# atmega_embedded_main.net
KiCad netlist of a schematic drawn in EAGLE
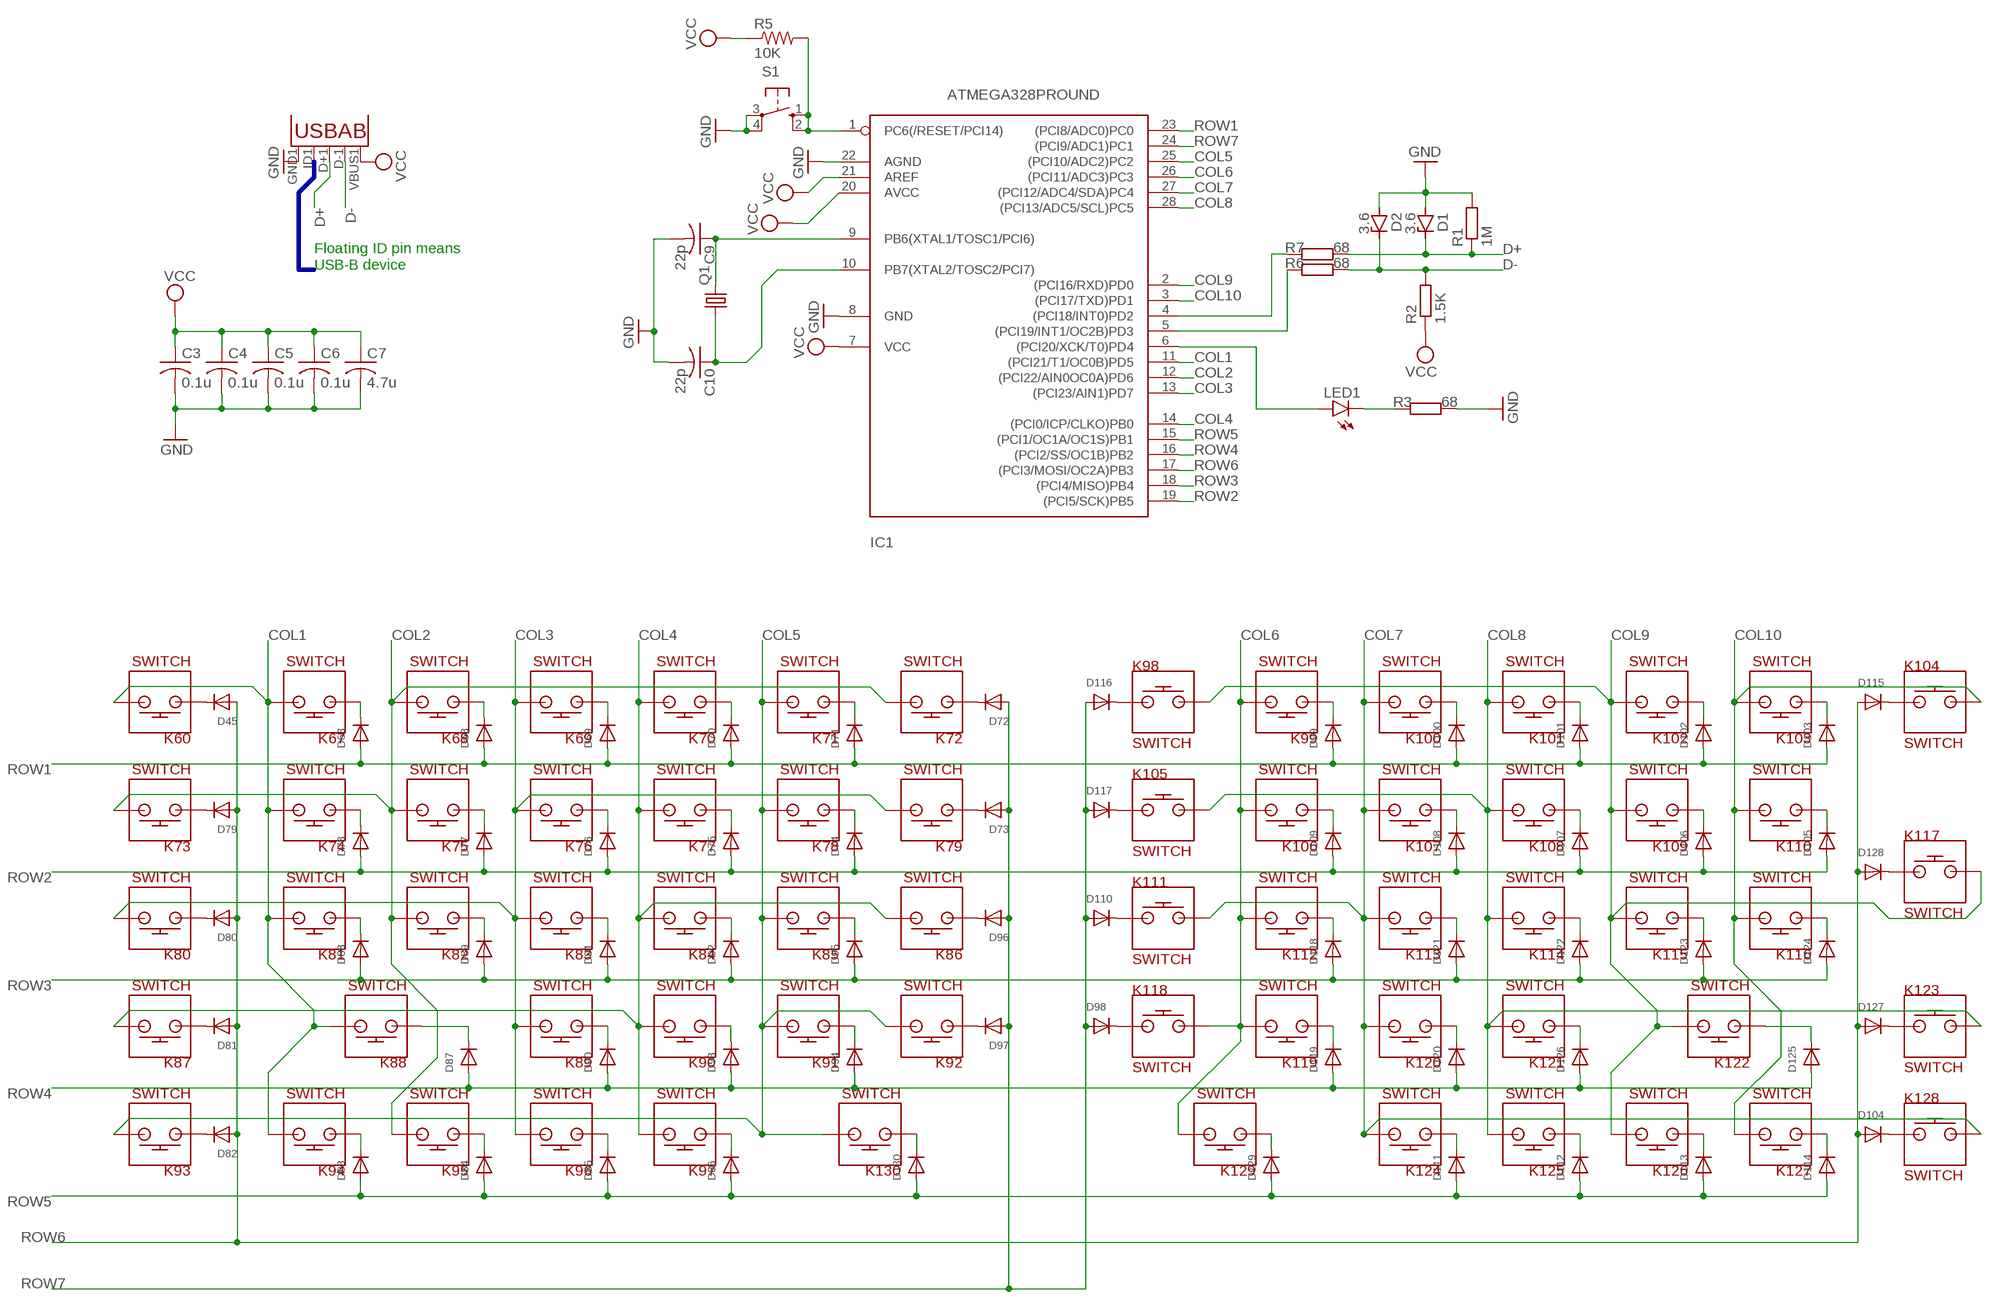
[diagram p0: schematic, sheet 1]

(export (version "E")
  (design (tool "Eeschema 10.0.6"))
  (components
    (comp (ref "C3")
      (value "0.1u")
      (footprint "eagle-import:C0805")
      (libsource (lib "eagle-import") (part "C-USC0805"))
    )
    (comp (ref "C4")
      (value "0.1u")
      (footprint "eagle-import:C0805")
      (libsource (lib "eagle-import") (part "C-USC0805"))
    )
    (comp (ref "C5")
      (value "0.1u")
      (footprint "eagle-import:C0805")
      (libsource (lib "eagle-import") (part "C-USC0805"))
    )
    (comp (ref "C6")
      (value "0.1u")
      (footprint "eagle-import:C0805")
      (libsource (lib "eagle-import") (part "C-USC0805"))
    )
    (comp (ref "C7")
      (value "4.7u")
      (footprint "eagle-import:C0805")
      (libsource (lib "eagle-import") (part "C-USC0805"))
    )
    (comp (ref "C9")
      (value "22p")
      (footprint "eagle-import:C0805")
      (libsource (lib "eagle-import") (part "C-USC0805"))
    )
    (comp (ref "C10")
      (value "22p")
      (footprint "eagle-import:C0805")
      (libsource (lib "eagle-import") (part "C-USC0805"))
    )
    (comp (ref "D1")
      (value "3.6")
      (footprint "eagle-import:SMB")
      (libsource (lib "eagle-import") (part "ZENER-DIODESMB"))
    )
    (comp (ref "D2")
      (value "3.6")
      (footprint "eagle-import:SMB")
      (libsource (lib "eagle-import") (part "ZENER-DIODESMB"))
    )
    (comp (ref "D45")
      (value "DIODESMA")
      (footprint "eagle-import:SMADIODE")
      (libsource (lib "eagle-import") (part "DIODESMA"))
    )
    (comp (ref "D63")
      (value "DIODESMA")
      (footprint "eagle-import:SMADIODE")
      (libsource (lib "eagle-import") (part "DIODESMA"))
    )
    (comp (ref "D68")
      (value "DIODESMA")
      (footprint "eagle-import:SMADIODE")
      (libsource (lib "eagle-import") (part "DIODESMA"))
    )
    (comp (ref "D69")
      (value "DIODESMA")
      (footprint "eagle-import:SMADIODE")
      (libsource (lib "eagle-import") (part "DIODESMA"))
    )
    (comp (ref "D70")
      (value "DIODESMA")
      (footprint "eagle-import:SMADIODE")
      (libsource (lib "eagle-import") (part "DIODESMA"))
    )
    (comp (ref "D71")
      (value "DIODESMA")
      (footprint "eagle-import:SMADIODE")
      (libsource (lib "eagle-import") (part "DIODESMA"))
    )
    (comp (ref "D72")
      (value "DIODESMA")
      (footprint "eagle-import:SMADIODE")
      (libsource (lib "eagle-import") (part "DIODESMA"))
    )
    (comp (ref "D73")
      (value "DIODESMA")
      (footprint "eagle-import:SMADIODE")
      (libsource (lib "eagle-import") (part "DIODESMA"))
    )
    (comp (ref "D74")
      (value "DIODESMA")
      (footprint "eagle-import:SMADIODE")
      (libsource (lib "eagle-import") (part "DIODESMA"))
    )
    (comp (ref "D75")
      (value "DIODESMA")
      (footprint "eagle-import:SMADIODE")
      (libsource (lib "eagle-import") (part "DIODESMA"))
    )
    (comp (ref "D76")
      (value "DIODESMA")
      (footprint "eagle-import:SMADIODE")
      (libsource (lib "eagle-import") (part "DIODESMA"))
    )
    (comp (ref "D77")
      (value "DIODESMA")
      (footprint "eagle-import:SMADIODE")
      (libsource (lib "eagle-import") (part "DIODESMA"))
    )
    (comp (ref "D78")
      (value "DIODESMA")
      (footprint "eagle-import:SMADIODE")
      (libsource (lib "eagle-import") (part "DIODESMA"))
    )
    (comp (ref "D79")
      (value "DIODESMA")
      (footprint "eagle-import:SMADIODE")
      (libsource (lib "eagle-import") (part "DIODESMA"))
    )
    (comp (ref "D80")
      (value "DIODESMA")
      (footprint "eagle-import:SMADIODE")
      (libsource (lib "eagle-import") (part "DIODESMA"))
    )
    (comp (ref "D81")
      (value "DIODESMA")
      (footprint "eagle-import:SMADIODE")
      (libsource (lib "eagle-import") (part "DIODESMA"))
    )
    (comp (ref "D82")
      (value "DIODESMA")
      (footprint "eagle-import:SMADIODE")
      (libsource (lib "eagle-import") (part "DIODESMA"))
    )
    (comp (ref "D83")
      (value "DIODESMA")
      (footprint "eagle-import:SMADIODE")
      (libsource (lib "eagle-import") (part "DIODESMA"))
    )
    (comp (ref "D84")
      (value "DIODESMA")
      (footprint "eagle-import:SMADIODE")
      (libsource (lib "eagle-import") (part "DIODESMA"))
    )
    (comp (ref "D85")
      (value "DIODESMA")
      (footprint "eagle-import:SMADIODE")
      (libsource (lib "eagle-import") (part "DIODESMA"))
    )
    (comp (ref "D86")
      (value "DIODESMA")
      (footprint "eagle-import:SMADIODE")
      (libsource (lib "eagle-import") (part "DIODESMA"))
    )
    (comp (ref "D87")
      (value "DIODESMA")
      (footprint "eagle-import:SMADIODE")
      (libsource (lib "eagle-import") (part "DIODESMA"))
    )
    (comp (ref "D88")
      (value "DIODESMA")
      (footprint "eagle-import:SMADIODE")
      (libsource (lib "eagle-import") (part "DIODESMA"))
    )
    (comp (ref "D89")
      (value "DIODESMA")
      (footprint "eagle-import:SMADIODE")
      (libsource (lib "eagle-import") (part "DIODESMA"))
    )
    (comp (ref "D90")
      (value "DIODESMA")
      (footprint "eagle-import:SMADIODE")
      (libsource (lib "eagle-import") (part "DIODESMA"))
    )
    (comp (ref "D91")
      (value "DIODESMA")
      (footprint "eagle-import:SMADIODE")
      (libsource (lib "eagle-import") (part "DIODESMA"))
    )
    (comp (ref "D92")
      (value "DIODESMA")
      (footprint "eagle-import:SMADIODE")
      (libsource (lib "eagle-import") (part "DIODESMA"))
    )
    (comp (ref "D93")
      (value "DIODESMA")
      (footprint "eagle-import:SMADIODE")
      (libsource (lib "eagle-import") (part "DIODESMA"))
    )
    (comp (ref "D94")
      (value "DIODESMA")
      (footprint "eagle-import:SMADIODE")
      (libsource (lib "eagle-import") (part "DIODESMA"))
    )
    (comp (ref "D95")
      (value "DIODESMA")
      (footprint "eagle-import:SMADIODE")
      (libsource (lib "eagle-import") (part "DIODESMA"))
    )
    (comp (ref "D96")
      (value "DIODESMA")
      (footprint "eagle-import:SMADIODE")
      (libsource (lib "eagle-import") (part "DIODESMA"))
    )
    (comp (ref "D97")
      (value "DIODESMA")
      (footprint "eagle-import:SMADIODE")
      (libsource (lib "eagle-import") (part "DIODESMA"))
    )
    (comp (ref "D98")
      (value "DIODESMA")
      (footprint "eagle-import:SMADIODE")
      (libsource (lib "eagle-import") (part "DIODESMA"))
    )
    (comp (ref "D99")
      (value "DIODESMA")
      (footprint "eagle-import:SMADIODE")
      (libsource (lib "eagle-import") (part "DIODESMA"))
    )
    (comp (ref "D100")
      (value "DIODESMA")
      (footprint "eagle-import:SMADIODE")
      (libsource (lib "eagle-import") (part "DIODESMA"))
    )
    (comp (ref "D101")
      (value "DIODESMA")
      (footprint "eagle-import:SMADIODE")
      (libsource (lib "eagle-import") (part "DIODESMA"))
    )
    (comp (ref "D102")
      (value "DIODESMA")
      (footprint "eagle-import:SMADIODE")
      (libsource (lib "eagle-import") (part "DIODESMA"))
    )
    (comp (ref "D103")
      (value "DIODESMA")
      (footprint "eagle-import:SMADIODE")
      (libsource (lib "eagle-import") (part "DIODESMA"))
    )
    (comp (ref "D104")
      (value "DIODESMA")
      (footprint "eagle-import:SMADIODE")
      (libsource (lib "eagle-import") (part "DIODESMA"))
    )
    (comp (ref "D105")
      (value "DIODESMA")
      (footprint "eagle-import:SMADIODE")
      (libsource (lib "eagle-import") (part "DIODESMA"))
    )
    (comp (ref "D106")
      (value "DIODESMA")
      (footprint "eagle-import:SMADIODE")
      (libsource (lib "eagle-import") (part "DIODESMA"))
    )
    (comp (ref "D107")
      (value "DIODESMA")
      (footprint "eagle-import:SMADIODE")
      (libsource (lib "eagle-import") (part "DIODESMA"))
    )
    (comp (ref "D108")
      (value "DIODESMA")
      (footprint "eagle-import:SMADIODE")
      (libsource (lib "eagle-import") (part "DIODESMA"))
    )
    (comp (ref "D109")
      (value "DIODESMA")
      (footprint "eagle-import:SMADIODE")
      (libsource (lib "eagle-import") (part "DIODESMA"))
    )
    (comp (ref "D110")
      (value "DIODESMA")
      (footprint "eagle-import:SMADIODE")
      (libsource (lib "eagle-import") (part "DIODESMA"))
    )
    (comp (ref "D111")
      (value "DIODESMA")
      (footprint "eagle-import:SMADIODE")
      (libsource (lib "eagle-import") (part "DIODESMA"))
    )
    (comp (ref "D112")
      (value "DIODESMA")
      (footprint "eagle-import:SMADIODE")
      (libsource (lib "eagle-import") (part "DIODESMA"))
    )
    (comp (ref "D113")
      (value "DIODESMA")
      (footprint "eagle-import:SMADIODE")
      (libsource (lib "eagle-import") (part "DIODESMA"))
    )
    (comp (ref "D114")
      (value "DIODESMA")
      (footprint "eagle-import:SMADIODE")
      (libsource (lib "eagle-import") (part "DIODESMA"))
    )
    (comp (ref "D115")
      (value "DIODESMA")
      (footprint "eagle-import:SMADIODE")
      (libsource (lib "eagle-import") (part "DIODESMA"))
    )
    (comp (ref "D116")
      (value "DIODESMA")
      (footprint "eagle-import:SMADIODE")
      (libsource (lib "eagle-import") (part "DIODESMA"))
    )
    (comp (ref "D117")
      (value "DIODESMA")
      (footprint "eagle-import:SMADIODE")
      (libsource (lib "eagle-import") (part "DIODESMA"))
    )
    (comp (ref "D118")
      (value "DIODESMA")
      (footprint "eagle-import:SMADIODE")
      (libsource (lib "eagle-import") (part "DIODESMA"))
    )
    (comp (ref "D119")
      (value "DIODESMA")
      (footprint "eagle-import:SMADIODE")
      (libsource (lib "eagle-import") (part "DIODESMA"))
    )
    (comp (ref "D120")
      (value "DIODESMA")
      (footprint "eagle-import:SMADIODE")
      (libsource (lib "eagle-import") (part "DIODESMA"))
    )
    (comp (ref "D121")
      (value "DIODESMA")
      (footprint "eagle-import:SMADIODE")
      (libsource (lib "eagle-import") (part "DIODESMA"))
    )
    (comp (ref "D122")
      (value "DIODESMA")
      (footprint "eagle-import:SMADIODE")
      (libsource (lib "eagle-import") (part "DIODESMA"))
    )
    (comp (ref "D123")
      (value "DIODESMA")
      (footprint "eagle-import:SMADIODE")
      (libsource (lib "eagle-import") (part "DIODESMA"))
    )
    (comp (ref "D124")
      (value "DIODESMA")
      (footprint "eagle-import:SMADIODE")
      (libsource (lib "eagle-import") (part "DIODESMA"))
    )
    (comp (ref "D125")
      (value "DIODESMA")
      (footprint "eagle-import:SMADIODE")
      (libsource (lib "eagle-import") (part "DIODESMA"))
    )
    (comp (ref "D126")
      (value "DIODESMA")
      (footprint "eagle-import:SMADIODE")
      (libsource (lib "eagle-import") (part "DIODESMA"))
    )
    (comp (ref "D127")
      (value "DIODESMA")
      (footprint "eagle-import:SMADIODE")
      (libsource (lib "eagle-import") (part "DIODESMA"))
    )
    (comp (ref "D128")
      (value "DIODESMA")
      (footprint "eagle-import:SMADIODE")
      (libsource (lib "eagle-import") (part "DIODESMA"))
    )
    (comp (ref "D129")
      (value "DIODESMA")
      (footprint "eagle-import:SMADIODE")
      (libsource (lib "eagle-import") (part "DIODESMA"))
    )
    (comp (ref "D130")
      (value "DIODESMA")
      (footprint "eagle-import:SMADIODE")
      (libsource (lib "eagle-import") (part "DIODESMA"))
    )
    (comp (ref "IC1")
      (value "ATMEGA328PROUND")
      (footprint "eagle-import:DIL28-3-ROUND")
      (libsource (lib "eagle-import") (part "ATMEGA328PROUND"))
    )
    (comp (ref "K60")
      (value "SWITCH")
      (footprint "eagle-import:KAILH_LOW_PROFILE")
      (libsource (lib "eagle-import") (part "SWITCH"))
    )
    (comp (ref "K67")
      (value "SWITCH")
      (footprint "eagle-import:KAILH_LOW_PROFILE")
      (libsource (lib "eagle-import") (part "SWITCH"))
    )
    (comp (ref "K68")
      (value "SWITCH")
      (footprint "eagle-import:KAILH_LOW_PROFILE")
      (libsource (lib "eagle-import") (part "SWITCH"))
    )
    (comp (ref "K69")
      (value "SWITCH")
      (footprint "eagle-import:KAILH_LOW_PROFILE")
      (libsource (lib "eagle-import") (part "SWITCH"))
    )
    (comp (ref "K70")
      (value "SWITCH")
      (footprint "eagle-import:KAILH_LOW_PROFILE")
      (libsource (lib "eagle-import") (part "SWITCH"))
    )
    (comp (ref "K71")
      (value "SWITCH")
      (footprint "eagle-import:KAILH_LOW_PROFILE")
      (libsource (lib "eagle-import") (part "SWITCH"))
    )
    (comp (ref "K72")
      (value "SWITCH")
      (footprint "eagle-import:KAILH_LOW_PROFILE")
      (libsource (lib "eagle-import") (part "SWITCH"))
    )
    (comp (ref "K73")
      (value "SWITCH")
      (footprint "eagle-import:KAILH_LOW_PROFILE")
      (libsource (lib "eagle-import") (part "SWITCH"))
    )
    (comp (ref "K74")
      (value "SWITCH")
      (footprint "eagle-import:KAILH_LOW_PROFILE")
      (libsource (lib "eagle-import") (part "SWITCH"))
    )
    (comp (ref "K75")
      (value "SWITCH")
      (footprint "eagle-import:KAILH_LOW_PROFILE")
      (libsource (lib "eagle-import") (part "SWITCH"))
    )
    (comp (ref "K76")
      (value "SWITCH")
      (footprint "eagle-import:KAILH_LOW_PROFILE")
      (libsource (lib "eagle-import") (part "SWITCH"))
    )
    (comp (ref "K77")
      (value "SWITCH")
      (footprint "eagle-import:KAILH_LOW_PROFILE")
      (libsource (lib "eagle-import") (part "SWITCH"))
    )
    (comp (ref "K78")
      (value "SWITCH")
      (footprint "eagle-import:KAILH_LOW_PROFILE")
      (libsource (lib "eagle-import") (part "SWITCH"))
    )
    (comp (ref "K79")
      (value "SWITCH")
      (footprint "eagle-import:KAILH_LOW_PROFILE")
      (libsource (lib "eagle-import") (part "SWITCH"))
    )
    (comp (ref "K80")
      (value "SWITCH")
      (footprint "eagle-import:KAILH_LOW_PROFILE")
      (libsource (lib "eagle-import") (part "SWITCH"))
    )
    (comp (ref "K81")
      (value "SWITCH")
      (footprint "eagle-import:KAILH_LOW_PROFILE")
      (libsource (lib "eagle-import") (part "SWITCH"))
    )
    (comp (ref "K82")
      (value "SWITCH")
      (footprint "eagle-import:KAILH_LOW_PROFILE")
      (libsource (lib "eagle-import") (part "SWITCH"))
    )
    (comp (ref "K83")
      (value "SWITCH")
      (footprint "eagle-import:KAILH_LOW_PROFILE")
      (libsource (lib "eagle-import") (part "SWITCH"))
    )
    (comp (ref "K84")
      (value "SWITCH")
      (footprint "eagle-import:KAILH_LOW_PROFILE")
      (libsource (lib "eagle-import") (part "SWITCH"))
    )
    (comp (ref "K85")
      (value "SWITCH")
      (footprint "eagle-import:KAILH_LOW_PROFILE")
      (libsource (lib "eagle-import") (part "SWITCH"))
    )
    (comp (ref "K86")
      (value "SWITCH")
      (footprint "eagle-import:KAILH_LOW_PROFILE")
      (libsource (lib "eagle-import") (part "SWITCH"))
    )
    (comp (ref "K87")
      (value "SWITCH")
      (footprint "eagle-import:KAILH_LOW_PROFILE")
      (libsource (lib "eagle-import") (part "SWITCH"))
    )
    (comp (ref "K88")
      (value "SWITCH")
      (footprint "eagle-import:KAILH_LOW_PROFILE")
      (libsource (lib "eagle-import") (part "SWITCH"))
    )
    (comp (ref "K89")
      (value "SWITCH")
      (footprint "eagle-import:KAILH_LOW_PROFILE")
      (libsource (lib "eagle-import") (part "SWITCH"))
    )
    (comp (ref "K90")
      (value "SWITCH")
      (footprint "eagle-import:KAILH_LOW_PROFILE")
      (libsource (lib "eagle-import") (part "SWITCH"))
    )
    (comp (ref "K91")
      (value "SWITCH")
      (footprint "eagle-import:KAILH_LOW_PROFILE")
      (libsource (lib "eagle-import") (part "SWITCH"))
    )
    (comp (ref "K92")
      (value "SWITCH")
      (footprint "eagle-import:KAILH_LOW_PROFILE")
      (libsource (lib "eagle-import") (part "SWITCH"))
    )
    (comp (ref "K93")
      (value "SWITCH")
      (footprint "eagle-import:KAILH_LOW_PROFILE")
      (libsource (lib "eagle-import") (part "SWITCH"))
    )
    (comp (ref "K94")
      (value "SWITCH")
      (footprint "eagle-import:KAILH_LOW_PROFILE")
      (libsource (lib "eagle-import") (part "SWITCH"))
    )
    (comp (ref "K95")
      (value "SWITCH")
      (footprint "eagle-import:KAILH_LOW_PROFILE")
      (libsource (lib "eagle-import") (part "SWITCH"))
    )
    (comp (ref "K96")
      (value "SWITCH")
      (footprint "eagle-import:KAILH_LOW_PROFILE")
      (libsource (lib "eagle-import") (part "SWITCH"))
    )
    (comp (ref "K97")
      (value "SWITCH")
      (footprint "eagle-import:KAILH_LOW_PROFILE")
      (libsource (lib "eagle-import") (part "SWITCH"))
    )
    (comp (ref "K98")
      (value "SWITCH")
      (footprint "eagle-import:KAILH_LOW_PROFILE")
      (libsource (lib "eagle-import") (part "SWITCH"))
    )
    (comp (ref "K99")
      (value "SWITCH")
      (footprint "eagle-import:KAILH_LOW_PROFILE")
      (libsource (lib "eagle-import") (part "SWITCH"))
    )
    (comp (ref "K100")
      (value "SWITCH")
      (footprint "eagle-import:KAILH_LOW_PROFILE")
      (libsource (lib "eagle-import") (part "SWITCH"))
    )
    (comp (ref "K101")
      (value "SWITCH")
      (footprint "eagle-import:KAILH_LOW_PROFILE")
      (libsource (lib "eagle-import") (part "SWITCH"))
    )
    (comp (ref "K102")
      (value "SWITCH")
      (footprint "eagle-import:KAILH_LOW_PROFILE")
      (libsource (lib "eagle-import") (part "SWITCH"))
    )
    (comp (ref "K103")
      (value "SWITCH")
      (footprint "eagle-import:KAILH_LOW_PROFILE")
      (libsource (lib "eagle-import") (part "SWITCH"))
    )
    (comp (ref "K104")
      (value "SWITCH")
      (footprint "eagle-import:KAILH_LOW_PROFILE")
      (libsource (lib "eagle-import") (part "SWITCH"))
    )
    (comp (ref "K105")
      (value "SWITCH")
      (footprint "eagle-import:KAILH_LOW_PROFILE")
      (libsource (lib "eagle-import") (part "SWITCH"))
    )
    (comp (ref "K106")
      (value "SWITCH")
      (footprint "eagle-import:KAILH_LOW_PROFILE")
      (libsource (lib "eagle-import") (part "SWITCH"))
    )
    (comp (ref "K107")
      (value "SWITCH")
      (footprint "eagle-import:KAILH_LOW_PROFILE")
      (libsource (lib "eagle-import") (part "SWITCH"))
    )
    (comp (ref "K108")
      (value "SWITCH")
      (footprint "eagle-import:KAILH_LOW_PROFILE")
      (libsource (lib "eagle-import") (part "SWITCH"))
    )
    (comp (ref "K109")
      (value "SWITCH")
      (footprint "eagle-import:KAILH_LOW_PROFILE")
      (libsource (lib "eagle-import") (part "SWITCH"))
    )
    (comp (ref "K110")
      (value "SWITCH")
      (footprint "eagle-import:KAILH_LOW_PROFILE")
      (libsource (lib "eagle-import") (part "SWITCH"))
    )
    (comp (ref "K111")
      (value "SWITCH")
      (footprint "eagle-import:KAILH_LOW_PROFILE")
      (libsource (lib "eagle-import") (part "SWITCH"))
    )
    (comp (ref "K112")
      (value "SWITCH")
      (footprint "eagle-import:KAILH_LOW_PROFILE")
      (libsource (lib "eagle-import") (part "SWITCH"))
    )
    (comp (ref "K113")
      (value "SWITCH")
      (footprint "eagle-import:KAILH_LOW_PROFILE")
      (libsource (lib "eagle-import") (part "SWITCH"))
    )
    (comp (ref "K114")
      (value "SWITCH")
      (footprint "eagle-import:KAILH_LOW_PROFILE")
      (libsource (lib "eagle-import") (part "SWITCH"))
    )
    (comp (ref "K115")
      (value "SWITCH")
      (footprint "eagle-import:KAILH_LOW_PROFILE")
      (libsource (lib "eagle-import") (part "SWITCH"))
    )
    (comp (ref "K116")
      (value "SWITCH")
      (footprint "eagle-import:KAILH_LOW_PROFILE")
      (libsource (lib "eagle-import") (part "SWITCH"))
    )
    (comp (ref "K117")
      (value "SWITCH")
      (footprint "eagle-import:KAILH_LOW_PROFILE")
      (libsource (lib "eagle-import") (part "SWITCH"))
    )
    (comp (ref "K118")
      (value "SWITCH")
      (footprint "eagle-import:KAILH_LOW_PROFILE")
      (libsource (lib "eagle-import") (part "SWITCH"))
    )
    (comp (ref "K119")
      (value "SWITCH")
      (footprint "eagle-import:KAILH_LOW_PROFILE")
      (libsource (lib "eagle-import") (part "SWITCH"))
    )
    (comp (ref "K120")
      (value "SWITCH")
      (footprint "eagle-import:KAILH_LOW_PROFILE")
      (libsource (lib "eagle-import") (part "SWITCH"))
    )
    (comp (ref "K121")
      (value "SWITCH")
      (footprint "eagle-import:KAILH_LOW_PROFILE")
      (libsource (lib "eagle-import") (part "SWITCH"))
    )
    (comp (ref "K122")
      (value "SWITCH")
      (footprint "eagle-import:KAILH_LOW_PROFILE")
      (libsource (lib "eagle-import") (part "SWITCH"))
    )
    (comp (ref "K123")
      (value "SWITCH")
      (footprint "eagle-import:KAILH_LOW_PROFILE")
      (libsource (lib "eagle-import") (part "SWITCH"))
    )
    (comp (ref "K124")
      (value "SWITCH")
      (footprint "eagle-import:KAILH_LOW_PROFILE")
      (libsource (lib "eagle-import") (part "SWITCH"))
    )
    (comp (ref "K125")
      (value "SWITCH")
      (footprint "eagle-import:KAILH_LOW_PROFILE")
      (libsource (lib "eagle-import") (part "SWITCH"))
    )
    (comp (ref "K126")
      (value "SWITCH")
      (footprint "eagle-import:KAILH_LOW_PROFILE")
      (libsource (lib "eagle-import") (part "SWITCH"))
    )
    (comp (ref "K127")
      (value "SWITCH")
      (footprint "eagle-import:KAILH_LOW_PROFILE")
      (libsource (lib "eagle-import") (part "SWITCH"))
    )
    (comp (ref "K128")
      (value "SWITCH")
      (footprint "eagle-import:KAILH_LOW_PROFILE")
      (libsource (lib "eagle-import") (part "SWITCH"))
    )
    (comp (ref "K129")
      (value "SWITCH")
      (footprint "eagle-import:KAILH_LOW_PROFILE")
      (libsource (lib "eagle-import") (part "SWITCH"))
    )
    (comp (ref "K130")
      (value "SWITCH")
      (footprint "eagle-import:KAILH_LOW_PROFILE")
      (libsource (lib "eagle-import") (part "SWITCH"))
    )
    (comp (ref "LED1")
      (value "LEDCHIPLED_1206")
      (footprint "eagle-import:CHIPLED_1206")
      (libsource (lib "eagle-import") (part "LEDCHIPLED_1206"))
    )
    (comp (ref "Q1")
      (value "CRYSTALHC49S")
      (footprint "eagle-import:HC49_S")
      (libsource (lib "eagle-import") (part "CRYSTALHC49S"))
    )
    (comp (ref "R1")
      (value "1M")
      (footprint "eagle-import:R1206")
      (libsource (lib "eagle-import") (part "RR1206"))
    )
    (comp (ref "R2")
      (value "1.5K")
      (footprint "eagle-import:R1206")
      (libsource (lib "eagle-import") (part "RR1206"))
    )
    (comp (ref "R3")
      (value "68")
      (footprint "eagle-import:R1206")
      (libsource (lib "eagle-import") (part "RR1206"))
    )
    (comp (ref "R5")
      (value "10K")
      (footprint "eagle-import:M0805")
      (libsource (lib "eagle-import") (part "R-US_M0805"))
    )
    (comp (ref "R6")
      (value "68")
      (footprint "eagle-import:R1206")
      (libsource (lib "eagle-import") (part "RR1206"))
    )
    (comp (ref "R7")
      (value "68")
      (footprint "eagle-import:R1206")
      (libsource (lib "eagle-import") (part "RR1206"))
    )
    (comp (ref "S1")
      (value "10-XX")
      (footprint "eagle-import:B3F-10XX")
      (fields (field (name "MPN") "B3F-1000"))
      (libsource (lib "eagle-import") (part "10-XX"))
    )
    (comp (ref "U1")
      (value "USB\"\"")
      (footprint "eagle-import:USB-MICRO-SMD")
      (libsource (lib "eagle-import") (part "USB{dblquote}{dblquote}"))
    )
  )
  (nets
    (net (code "1") (name "/COL1") (class "Default")
      (node (ref "IC1") (pin "11") (pinfunction "(PCI21/T1/OC0B)PD5_11") (pintype "bidirectional"))
      (node (ref "K60") (pin "P$2") (pinfunction "P$2_P$2") (pintype "bidirectional"))
      (node (ref "K67") (pin "P$2") (pinfunction "P$2_P$2") (pintype "bidirectional"))
      (node (ref "K74") (pin "P$2") (pinfunction "P$2_P$2") (pintype "bidirectional"))
      (node (ref "K81") (pin "P$2") (pinfunction "P$2_P$2") (pintype "bidirectional"))
      (node (ref "K88") (pin "P$2") (pinfunction "P$2_P$2") (pintype "bidirectional"))
      (node (ref "K94") (pin "P$2") (pinfunction "P$2_P$2") (pintype "bidirectional"))
    )
    (net (code "2") (name "/COL2") (class "Default")
      (node (ref "IC1") (pin "12") (pinfunction "(PCI22/AIN0OC0A)PD6_12") (pintype "bidirectional"))
      (node (ref "K68") (pin "P$2") (pinfunction "P$2_P$2") (pintype "bidirectional"))
      (node (ref "K72") (pin "P$2") (pinfunction "P$2_P$2") (pintype "bidirectional"))
      (node (ref "K73") (pin "P$2") (pinfunction "P$2_P$2") (pintype "bidirectional"))
      (node (ref "K75") (pin "P$2") (pinfunction "P$2_P$2") (pintype "bidirectional"))
      (node (ref "K82") (pin "P$2") (pinfunction "P$2_P$2") (pintype "bidirectional"))
      (node (ref "K95") (pin "P$2") (pinfunction "P$2_P$2") (pintype "bidirectional"))
    )
    (net (code "3") (name "/COL3") (class "Default")
      (node (ref "IC1") (pin "13") (pinfunction "(PCI23/AIN1)PD7_13") (pintype "bidirectional"))
      (node (ref "K69") (pin "P$2") (pinfunction "P$2_P$2") (pintype "bidirectional"))
      (node (ref "K76") (pin "P$2") (pinfunction "P$2_P$2") (pintype "bidirectional"))
      (node (ref "K79") (pin "P$2") (pinfunction "P$2_P$2") (pintype "bidirectional"))
      (node (ref "K80") (pin "P$2") (pinfunction "P$2_P$2") (pintype "bidirectional"))
      (node (ref "K83") (pin "P$2") (pinfunction "P$2_P$2") (pintype "bidirectional"))
      (node (ref "K89") (pin "P$2") (pinfunction "P$2_P$2") (pintype "bidirectional"))
      (node (ref "K96") (pin "P$2") (pinfunction "P$2_P$2") (pintype "bidirectional"))
    )
    (net (code "4") (name "/COL4") (class "Default")
      (node (ref "IC1") (pin "14") (pinfunction "(PCI0/ICP/CLKO)PB0_14") (pintype "bidirectional"))
      (node (ref "K70") (pin "P$2") (pinfunction "P$2_P$2") (pintype "bidirectional"))
      (node (ref "K77") (pin "P$2") (pinfunction "P$2_P$2") (pintype "bidirectional"))
      (node (ref "K84") (pin "P$2") (pinfunction "P$2_P$2") (pintype "bidirectional"))
      (node (ref "K86") (pin "P$2") (pinfunction "P$2_P$2") (pintype "bidirectional"))
      (node (ref "K87") (pin "P$2") (pinfunction "P$2_P$2") (pintype "bidirectional"))
      (node (ref "K90") (pin "P$2") (pinfunction "P$2_P$2") (pintype "bidirectional"))
      (node (ref "K97") (pin "P$2") (pinfunction "P$2_P$2") (pintype "bidirectional"))
    )
    (net (code "5") (name "/COL5") (class "Default")
      (node (ref "IC1") (pin "25") (pinfunction "(PCI10/ADC2)PC2_25") (pintype "bidirectional"))
      (node (ref "K130") (pin "P$2") (pinfunction "P$2_P$2") (pintype "bidirectional"))
      (node (ref "K71") (pin "P$2") (pinfunction "P$2_P$2") (pintype "bidirectional"))
      (node (ref "K78") (pin "P$2") (pinfunction "P$2_P$2") (pintype "bidirectional"))
      (node (ref "K85") (pin "P$2") (pinfunction "P$2_P$2") (pintype "bidirectional"))
      (node (ref "K91") (pin "P$2") (pinfunction "P$2_P$2") (pintype "bidirectional"))
      (node (ref "K92") (pin "P$2") (pinfunction "P$2_P$2") (pintype "bidirectional"))
      (node (ref "K93") (pin "P$2") (pinfunction "P$2_P$2") (pintype "bidirectional"))
    )
    (net (code "6") (name "/COL6") (class "Default")
      (node (ref "IC1") (pin "26") (pinfunction "(PCI11/ADC3)PC3_26") (pintype "bidirectional"))
      (node (ref "K106") (pin "P$2") (pinfunction "P$2_P$2") (pintype "bidirectional"))
      (node (ref "K112") (pin "P$2") (pinfunction "P$2_P$2") (pintype "bidirectional"))
      (node (ref "K118") (pin "P$2") (pinfunction "P$2_P$2") (pintype "bidirectional"))
      (node (ref "K119") (pin "P$2") (pinfunction "P$2_P$2") (pintype "bidirectional"))
      (node (ref "K129") (pin "P$2") (pinfunction "P$2_P$2") (pintype "bidirectional"))
      (node (ref "K99") (pin "P$2") (pinfunction "P$2_P$2") (pintype "bidirectional"))
    )
    (net (code "7") (name "/COL7") (class "Default")
      (node (ref "IC1") (pin "27") (pinfunction "(PCI12/ADC4/SDA)PC4_27") (pintype "bidirectional"))
      (node (ref "K100") (pin "P$2") (pinfunction "P$2_P$2") (pintype "bidirectional"))
      (node (ref "K107") (pin "P$2") (pinfunction "P$2_P$2") (pintype "bidirectional"))
      (node (ref "K111") (pin "P$2") (pinfunction "P$2_P$2") (pintype "bidirectional"))
      (node (ref "K113") (pin "P$2") (pinfunction "P$2_P$2") (pintype "bidirectional"))
      (node (ref "K120") (pin "P$2") (pinfunction "P$2_P$2") (pintype "bidirectional"))
      (node (ref "K124") (pin "P$2") (pinfunction "P$2_P$2") (pintype "bidirectional"))
      (node (ref "K128") (pin "P$2") (pinfunction "P$2_P$2") (pintype "bidirectional"))
    )
    (net (code "8") (name "/COL8") (class "Default")
      (node (ref "IC1") (pin "28") (pinfunction "(PCI13/ADC5/SCL)PC5_28") (pintype "bidirectional"))
      (node (ref "K101") (pin "P$2") (pinfunction "P$2_P$2") (pintype "bidirectional"))
      (node (ref "K105") (pin "P$2") (pinfunction "P$2_P$2") (pintype "bidirectional"))
      (node (ref "K108") (pin "P$2") (pinfunction "P$2_P$2") (pintype "bidirectional"))
      (node (ref "K114") (pin "P$2") (pinfunction "P$2_P$2") (pintype "bidirectional"))
      (node (ref "K121") (pin "P$2") (pinfunction "P$2_P$2") (pintype "bidirectional"))
      (node (ref "K123") (pin "P$2") (pinfunction "P$2_P$2") (pintype "bidirectional"))
      (node (ref "K125") (pin "P$2") (pinfunction "P$2_P$2") (pintype "bidirectional"))
    )
    (net (code "9") (name "/COL9") (class "Default")
      (node (ref "IC1") (pin "2") (pinfunction "(PCI16/RXD)PD0_2") (pintype "bidirectional"))
      (node (ref "K102") (pin "P$2") (pinfunction "P$2_P$2") (pintype "bidirectional"))
      (node (ref "K109") (pin "P$2") (pinfunction "P$2_P$2") (pintype "bidirectional"))
      (node (ref "K115") (pin "P$2") (pinfunction "P$2_P$2") (pintype "bidirectional"))
      (node (ref "K117") (pin "P$2") (pinfunction "P$2_P$2") (pintype "bidirectional"))
      (node (ref "K122") (pin "P$2") (pinfunction "P$2_P$2") (pintype "bidirectional"))
      (node (ref "K126") (pin "P$2") (pinfunction "P$2_P$2") (pintype "bidirectional"))
      (node (ref "K98") (pin "P$2") (pinfunction "P$2_P$2") (pintype "bidirectional"))
    )
    (net (code "10") (name "/COL10") (class "Default")
      (node (ref "IC1") (pin "3") (pinfunction "(PCI17/TXD)PD1_3") (pintype "bidirectional"))
      (node (ref "K103") (pin "P$2") (pinfunction "P$2_P$2") (pintype "bidirectional"))
      (node (ref "K104") (pin "P$2") (pinfunction "P$2_P$2") (pintype "bidirectional"))
      (node (ref "K110") (pin "P$2") (pinfunction "P$2_P$2") (pintype "bidirectional"))
      (node (ref "K116") (pin "P$2") (pinfunction "P$2_P$2") (pintype "bidirectional"))
      (node (ref "K127") (pin "P$2") (pinfunction "P$2_P$2") (pintype "bidirectional"))
    )
    (net (code "11") (name "/D+") (class "Default")
      (node (ref "D1") (pin "C") (pinfunction "C_C") (pintype "passive"))
      (node (ref "R1") (pin "1") (pinfunction "1_1") (pintype "passive"))
      (node (ref "R7") (pin "2") (pinfunction "2_2") (pintype "passive"))
      (node (ref "U1") (pin "D+1") (pinfunction "D+_D+1") (pintype "bidirectional"))
    )
    (net (code "12") (name "/D-") (class "Default")
      (node (ref "D2") (pin "C") (pinfunction "C_C") (pintype "passive"))
      (node (ref "R2") (pin "2") (pinfunction "2_2") (pintype "passive"))
      (node (ref "R6") (pin "2") (pinfunction "2_2") (pintype "passive"))
      (node (ref "U1") (pin "D-1") (pinfunction "D-_D-1") (pintype "bidirectional"))
    )
    (net (code "13") (name "/ROW1") (class "Default")
      (node (ref "D100") (pin "A") (pinfunction "A_A") (pintype "passive"))
      (node (ref "D101") (pin "A") (pinfunction "A_A") (pintype "passive"))
      (node (ref "D102") (pin "A") (pinfunction "A_A") (pintype "passive"))
      (node (ref "D103") (pin "A") (pinfunction "A_A") (pintype "passive"))
      (node (ref "D63") (pin "A") (pinfunction "A_A") (pintype "passive"))
      (node (ref "D68") (pin "A") (pinfunction "A_A") (pintype "passive"))
      (node (ref "D69") (pin "A") (pinfunction "A_A") (pintype "passive"))
      (node (ref "D70") (pin "A") (pinfunction "A_A") (pintype "passive"))
      (node (ref "D71") (pin "A") (pinfunction "A_A") (pintype "passive"))
      (node (ref "D99") (pin "A") (pinfunction "A_A") (pintype "passive"))
      (node (ref "IC1") (pin "23") (pinfunction "(PCI8/ADC0)PC0_23") (pintype "bidirectional"))
    )
    (net (code "14") (name "/ROW2") (class "Default")
      (node (ref "D105") (pin "A") (pinfunction "A_A") (pintype "passive"))
      (node (ref "D106") (pin "A") (pinfunction "A_A") (pintype "passive"))
      (node (ref "D107") (pin "A") (pinfunction "A_A") (pintype "passive"))
      (node (ref "D108") (pin "A") (pinfunction "A_A") (pintype "passive"))
      (node (ref "D109") (pin "A") (pinfunction "A_A") (pintype "passive"))
      (node (ref "D74") (pin "A") (pinfunction "A_A") (pintype "passive"))
      (node (ref "D75") (pin "A") (pinfunction "A_A") (pintype "passive"))
      (node (ref "D76") (pin "A") (pinfunction "A_A") (pintype "passive"))
      (node (ref "D77") (pin "A") (pinfunction "A_A") (pintype "passive"))
      (node (ref "D78") (pin "A") (pinfunction "A_A") (pintype "passive"))
      (node (ref "IC1") (pin "19") (pinfunction "(PCI5/SCK)PB5_19") (pintype "bidirectional"))
    )
    (net (code "15") (name "/ROW3") (class "Default")
      (node (ref "D118") (pin "A") (pinfunction "A_A") (pintype "passive"))
      (node (ref "D121") (pin "A") (pinfunction "A_A") (pintype "passive"))
      (node (ref "D122") (pin "A") (pinfunction "A_A") (pintype "passive"))
      (node (ref "D123") (pin "A") (pinfunction "A_A") (pintype "passive"))
      (node (ref "D124") (pin "A") (pinfunction "A_A") (pintype "passive"))
      (node (ref "D88") (pin "A") (pinfunction "A_A") (pintype "passive"))
      (node (ref "D89") (pin "A") (pinfunction "A_A") (pintype "passive"))
      (node (ref "D91") (pin "A") (pinfunction "A_A") (pintype "passive"))
      (node (ref "D92") (pin "A") (pinfunction "A_A") (pintype "passive"))
      (node (ref "D95") (pin "A") (pinfunction "A_A") (pintype "passive"))
      (node (ref "IC1") (pin "18") (pinfunction "(PCI4/MISO)PB4_18") (pintype "bidirectional"))
    )
    (net (code "16") (name "/ROW4") (class "Default")
      (node (ref "D119") (pin "A") (pinfunction "A_A") (pintype "passive"))
      (node (ref "D120") (pin "A") (pinfunction "A_A") (pintype "passive"))
      (node (ref "D125") (pin "A") (pinfunction "A_A") (pintype "passive"))
      (node (ref "D126") (pin "A") (pinfunction "A_A") (pintype "passive"))
      (node (ref "D87") (pin "A") (pinfunction "A_A") (pintype "passive"))
      (node (ref "D90") (pin "A") (pinfunction "A_A") (pintype "passive"))
      (node (ref "D93") (pin "A") (pinfunction "A_A") (pintype "passive"))
      (node (ref "D94") (pin "A") (pinfunction "A_A") (pintype "passive"))
      (node (ref "IC1") (pin "16") (pinfunction "(PCI2/SS/OC1B)PB2_16") (pintype "bidirectional"))
    )
    (net (code "17") (name "/ROW5") (class "Default")
      (node (ref "D111") (pin "A") (pinfunction "A_A") (pintype "passive"))
      (node (ref "D112") (pin "A") (pinfunction "A_A") (pintype "passive"))
      (node (ref "D113") (pin "A") (pinfunction "A_A") (pintype "passive"))
      (node (ref "D114") (pin "A") (pinfunction "A_A") (pintype "passive"))
      (node (ref "D129") (pin "A") (pinfunction "A_A") (pintype "passive"))
      (node (ref "D130") (pin "A") (pinfunction "A_A") (pintype "passive"))
      (node (ref "D83") (pin "A") (pinfunction "A_A") (pintype "passive"))
      (node (ref "D84") (pin "A") (pinfunction "A_A") (pintype "passive"))
      (node (ref "D85") (pin "A") (pinfunction "A_A") (pintype "passive"))
      (node (ref "D86") (pin "A") (pinfunction "A_A") (pintype "passive"))
      (node (ref "IC1") (pin "15") (pinfunction "(PCI1/OC1A/OC1S)PB1_15") (pintype "bidirectional"))
    )
    (net (code "18") (name "/ROW6") (class "Default")
      (node (ref "D104") (pin "A") (pinfunction "A_A") (pintype "passive"))
      (node (ref "D115") (pin "A") (pinfunction "A_A") (pintype "passive"))
      (node (ref "D127") (pin "A") (pinfunction "A_A") (pintype "passive"))
      (node (ref "D128") (pin "A") (pinfunction "A_A") (pintype "passive"))
      (node (ref "D45") (pin "A") (pinfunction "A_A") (pintype "passive"))
      (node (ref "D79") (pin "A") (pinfunction "A_A") (pintype "passive"))
      (node (ref "D80") (pin "A") (pinfunction "A_A") (pintype "passive"))
      (node (ref "D81") (pin "A") (pinfunction "A_A") (pintype "passive"))
      (node (ref "D82") (pin "A") (pinfunction "A_A") (pintype "passive"))
      (node (ref "IC1") (pin "17") (pinfunction "(PCI3/MOSI/OC2A)PB3_17") (pintype "bidirectional"))
    )
    (net (code "19") (name "/ROW7") (class "Default")
      (node (ref "D110") (pin "A") (pinfunction "A_A") (pintype "passive"))
      (node (ref "D116") (pin "A") (pinfunction "A_A") (pintype "passive"))
      (node (ref "D117") (pin "A") (pinfunction "A_A") (pintype "passive"))
      (node (ref "D72") (pin "A") (pinfunction "A_A") (pintype "passive"))
      (node (ref "D73") (pin "A") (pinfunction "A_A") (pintype "passive"))
      (node (ref "D96") (pin "A") (pinfunction "A_A") (pintype "passive"))
      (node (ref "D97") (pin "A") (pinfunction "A_A") (pintype "passive"))
      (node (ref "D98") (pin "A") (pinfunction "A_A") (pintype "passive"))
      (node (ref "IC1") (pin "24") (pinfunction "(PCI9/ADC1)PC1_24") (pintype "bidirectional"))
    )
    (net (code "20") (name "GND") (class "Default")
      (node (ref "C10") (pin "2") (pinfunction "2_2") (pintype "passive"))
      (node (ref "C3") (pin "2") (pinfunction "2_2") (pintype "passive"))
      (node (ref "C4") (pin "2") (pinfunction "2_2") (pintype "passive"))
      (node (ref "C5") (pin "2") (pinfunction "2_2") (pintype "passive"))
      (node (ref "C6") (pin "2") (pinfunction "2_2") (pintype "passive"))
      (node (ref "C7") (pin "2") (pinfunction "2_2") (pintype "passive"))
      (node (ref "C9") (pin "2") (pinfunction "2_2") (pintype "passive"))
      (node (ref "D1") (pin "A") (pinfunction "A_A") (pintype "passive"))
      (node (ref "D2") (pin "A") (pinfunction "A_A") (pintype "passive"))
      (node (ref "IC1") (pin "22") (pinfunction "AGND_22") (pintype "bidirectional"))
      (node (ref "IC1") (pin "8") (pinfunction "GND_8") (pintype "bidirectional"))
      (node (ref "R1") (pin "2") (pinfunction "2_2") (pintype "passive"))
      (node (ref "R3") (pin "2") (pinfunction "2_2") (pintype "passive"))
      (node (ref "S1") (pin "3") (pinfunction "P_3") (pintype "passive"))
      (node (ref "S1") (pin "4") (pinfunction "P1_4") (pintype "passive"))
      (node (ref "U1") (pin "GND1") (pinfunction "GND_GND1") (pintype "bidirectional"))
    )
    (net (code "21") (name "Net-(D45-PadC)") (class "Default")
      (node (ref "D45") (pin "C") (pinfunction "C_C") (pintype "passive"))
      (node (ref "K60") (pin "P$1") (pinfunction "P$1_P$1") (pintype "bidirectional"))
    )
    (net (code "22") (name "Net-(D63-PadC)") (class "Default")
      (node (ref "D63") (pin "C") (pinfunction "C_C") (pintype "passive"))
      (node (ref "K67") (pin "P$1") (pinfunction "P$1_P$1") (pintype "bidirectional"))
    )
    (net (code "23") (name "Net-(D68-PadC)") (class "Default")
      (node (ref "D68") (pin "C") (pinfunction "C_C") (pintype "passive"))
      (node (ref "K68") (pin "P$1") (pinfunction "P$1_P$1") (pintype "bidirectional"))
    )
    (net (code "24") (name "Net-(D69-PadC)") (class "Default")
      (node (ref "D69") (pin "C") (pinfunction "C_C") (pintype "passive"))
      (node (ref "K69") (pin "P$1") (pinfunction "P$1_P$1") (pintype "bidirectional"))
    )
    (net (code "25") (name "Net-(D70-PadC)") (class "Default")
      (node (ref "D70") (pin "C") (pinfunction "C_C") (pintype "passive"))
      (node (ref "K70") (pin "P$1") (pinfunction "P$1_P$1") (pintype "bidirectional"))
    )
    (net (code "26") (name "Net-(D71-PadC)") (class "Default")
      (node (ref "D71") (pin "C") (pinfunction "C_C") (pintype "passive"))
      (node (ref "K71") (pin "P$1") (pinfunction "P$1_P$1") (pintype "bidirectional"))
    )
    (net (code "27") (name "Net-(D72-PadC)") (class "Default")
      (node (ref "D72") (pin "C") (pinfunction "C_C") (pintype "passive"))
      (node (ref "K72") (pin "P$1") (pinfunction "P$1_P$1") (pintype "bidirectional"))
    )
    (net (code "28") (name "Net-(D73-PadC)") (class "Default")
      (node (ref "D73") (pin "C") (pinfunction "C_C") (pintype "passive"))
      (node (ref "K79") (pin "P$1") (pinfunction "P$1_P$1") (pintype "bidirectional"))
    )
    (net (code "29") (name "Net-(D74-PadC)") (class "Default")
      (node (ref "D74") (pin "C") (pinfunction "C_C") (pintype "passive"))
      (node (ref "K78") (pin "P$1") (pinfunction "P$1_P$1") (pintype "bidirectional"))
    )
    (net (code "30") (name "Net-(D75-PadC)") (class "Default")
      (node (ref "D75") (pin "C") (pinfunction "C_C") (pintype "passive"))
      (node (ref "K77") (pin "P$1") (pinfunction "P$1_P$1") (pintype "bidirectional"))
    )
    (net (code "31") (name "Net-(D76-PadC)") (class "Default")
      (node (ref "D76") (pin "C") (pinfunction "C_C") (pintype "passive"))
      (node (ref "K76") (pin "P$1") (pinfunction "P$1_P$1") (pintype "bidirectional"))
    )
    (net (code "32") (name "Net-(D77-PadC)") (class "Default")
      (node (ref "D77") (pin "C") (pinfunction "C_C") (pintype "passive"))
      (node (ref "K75") (pin "P$1") (pinfunction "P$1_P$1") (pintype "bidirectional"))
    )
    (net (code "33") (name "Net-(D78-PadC)") (class "Default")
      (node (ref "D78") (pin "C") (pinfunction "C_C") (pintype "passive"))
      (node (ref "K74") (pin "P$1") (pinfunction "P$1_P$1") (pintype "bidirectional"))
    )
    (net (code "34") (name "Net-(D79-PadC)") (class "Default")
      (node (ref "D79") (pin "C") (pinfunction "C_C") (pintype "passive"))
      (node (ref "K73") (pin "P$1") (pinfunction "P$1_P$1") (pintype "bidirectional"))
    )
    (net (code "35") (name "Net-(D80-PadC)") (class "Default")
      (node (ref "D80") (pin "C") (pinfunction "C_C") (pintype "passive"))
      (node (ref "K80") (pin "P$1") (pinfunction "P$1_P$1") (pintype "bidirectional"))
    )
    (net (code "36") (name "Net-(D81-PadC)") (class "Default")
      (node (ref "D81") (pin "C") (pinfunction "C_C") (pintype "passive"))
      (node (ref "K87") (pin "P$1") (pinfunction "P$1_P$1") (pintype "bidirectional"))
    )
    (net (code "37") (name "Net-(D82-PadC)") (class "Default")
      (node (ref "D82") (pin "C") (pinfunction "C_C") (pintype "passive"))
      (node (ref "K93") (pin "P$1") (pinfunction "P$1_P$1") (pintype "bidirectional"))
    )
    (net (code "38") (name "Net-(D83-PadC)") (class "Default")
      (node (ref "D83") (pin "C") (pinfunction "C_C") (pintype "passive"))
      (node (ref "K94") (pin "P$1") (pinfunction "P$1_P$1") (pintype "bidirectional"))
    )
    (net (code "39") (name "Net-(D84-PadC)") (class "Default")
      (node (ref "D84") (pin "C") (pinfunction "C_C") (pintype "passive"))
      (node (ref "K95") (pin "P$1") (pinfunction "P$1_P$1") (pintype "bidirectional"))
    )
    (net (code "40") (name "Net-(D85-PadC)") (class "Default")
      (node (ref "D85") (pin "C") (pinfunction "C_C") (pintype "passive"))
      (node (ref "K96") (pin "P$1") (pinfunction "P$1_P$1") (pintype "bidirectional"))
    )
    (net (code "41") (name "Net-(D86-PadC)") (class "Default")
      (node (ref "D86") (pin "C") (pinfunction "C_C") (pintype "passive"))
      (node (ref "K97") (pin "P$1") (pinfunction "P$1_P$1") (pintype "bidirectional"))
    )
    (net (code "42") (name "Net-(D87-PadC)") (class "Default")
      (node (ref "D87") (pin "C") (pinfunction "C_C") (pintype "passive"))
      (node (ref "K88") (pin "P$1") (pinfunction "P$1_P$1") (pintype "bidirectional"))
    )
    (net (code "43") (name "Net-(D88-PadC)") (class "Default")
      (node (ref "D88") (pin "C") (pinfunction "C_C") (pintype "passive"))
      (node (ref "K81") (pin "P$1") (pinfunction "P$1_P$1") (pintype "bidirectional"))
    )
    (net (code "44") (name "Net-(D89-PadC)") (class "Default")
      (node (ref "D89") (pin "C") (pinfunction "C_C") (pintype "passive"))
      (node (ref "K82") (pin "P$1") (pinfunction "P$1_P$1") (pintype "bidirectional"))
    )
    (net (code "45") (name "Net-(D90-PadC)") (class "Default")
      (node (ref "D90") (pin "C") (pinfunction "C_C") (pintype "passive"))
      (node (ref "K89") (pin "P$1") (pinfunction "P$1_P$1") (pintype "bidirectional"))
    )
    (net (code "46") (name "Net-(D91-PadC)") (class "Default")
      (node (ref "D91") (pin "C") (pinfunction "C_C") (pintype "passive"))
      (node (ref "K83") (pin "P$1") (pinfunction "P$1_P$1") (pintype "bidirectional"))
    )
    (net (code "47") (name "Net-(D92-PadC)") (class "Default")
      (node (ref "D92") (pin "C") (pinfunction "C_C") (pintype "passive"))
      (node (ref "K84") (pin "P$1") (pinfunction "P$1_P$1") (pintype "bidirectional"))
    )
    (net (code "48") (name "Net-(D93-PadC)") (class "Default")
      (node (ref "D93") (pin "C") (pinfunction "C_C") (pintype "passive"))
      (node (ref "K90") (pin "P$1") (pinfunction "P$1_P$1") (pintype "bidirectional"))
    )
    (net (code "49") (name "Net-(D94-PadC)") (class "Default")
      (node (ref "D94") (pin "C") (pinfunction "C_C") (pintype "passive"))
      (node (ref "K91") (pin "P$1") (pinfunction "P$1_P$1") (pintype "bidirectional"))
    )
    (net (code "50") (name "Net-(D95-PadC)") (class "Default")
      (node (ref "D95") (pin "C") (pinfunction "C_C") (pintype "passive"))
      (node (ref "K85") (pin "P$1") (pinfunction "P$1_P$1") (pintype "bidirectional"))
    )
    (net (code "51") (name "Net-(D96-PadC)") (class "Default")
      (node (ref "D96") (pin "C") (pinfunction "C_C") (pintype "passive"))
      (node (ref "K86") (pin "P$1") (pinfunction "P$1_P$1") (pintype "bidirectional"))
    )
    (net (code "52") (name "Net-(D97-PadC)") (class "Default")
      (node (ref "D97") (pin "C") (pinfunction "C_C") (pintype "passive"))
      (node (ref "K92") (pin "P$1") (pinfunction "P$1_P$1") (pintype "bidirectional"))
    )
    (net (code "53") (name "Net-(D98-PadC)") (class "Default")
      (node (ref "D98") (pin "C") (pinfunction "C_C") (pintype "passive"))
      (node (ref "K118") (pin "P$1") (pinfunction "P$1_P$1") (pintype "bidirectional"))
    )
    (net (code "54") (name "Net-(D99-PadC)") (class "Default")
      (node (ref "D99") (pin "C") (pinfunction "C_C") (pintype "passive"))
      (node (ref "K99") (pin "P$1") (pinfunction "P$1_P$1") (pintype "bidirectional"))
    )
    (net (code "55") (name "Net-(D100-PadC)") (class "Default")
      (node (ref "D100") (pin "C") (pinfunction "C_C") (pintype "passive"))
      (node (ref "K100") (pin "P$1") (pinfunction "P$1_P$1") (pintype "bidirectional"))
    )
    (net (code "56") (name "Net-(D101-PadC)") (class "Default")
      (node (ref "D101") (pin "C") (pinfunction "C_C") (pintype "passive"))
      (node (ref "K101") (pin "P$1") (pinfunction "P$1_P$1") (pintype "bidirectional"))
    )
    (net (code "57") (name "Net-(D102-PadC)") (class "Default")
      (node (ref "D102") (pin "C") (pinfunction "C_C") (pintype "passive"))
      (node (ref "K102") (pin "P$1") (pinfunction "P$1_P$1") (pintype "bidirectional"))
    )
    (net (code "58") (name "Net-(D103-PadC)") (class "Default")
      (node (ref "D103") (pin "C") (pinfunction "C_C") (pintype "passive"))
      (node (ref "K103") (pin "P$1") (pinfunction "P$1_P$1") (pintype "bidirectional"))
    )
    (net (code "59") (name "Net-(D104-PadC)") (class "Default")
      (node (ref "D104") (pin "C") (pinfunction "C_C") (pintype "passive"))
      (node (ref "K128") (pin "P$1") (pinfunction "P$1_P$1") (pintype "bidirectional"))
    )
    (net (code "60") (name "Net-(D105-PadC)") (class "Default")
      (node (ref "D105") (pin "C") (pinfunction "C_C") (pintype "passive"))
      (node (ref "K110") (pin "P$1") (pinfunction "P$1_P$1") (pintype "bidirectional"))
    )
    (net (code "61") (name "Net-(D106-PadC)") (class "Default")
      (node (ref "D106") (pin "C") (pinfunction "C_C") (pintype "passive"))
      (node (ref "K109") (pin "P$1") (pinfunction "P$1_P$1") (pintype "bidirectional"))
    )
    (net (code "62") (name "Net-(D107-PadC)") (class "Default")
      (node (ref "D107") (pin "C") (pinfunction "C_C") (pintype "passive"))
      (node (ref "K108") (pin "P$1") (pinfunction "P$1_P$1") (pintype "bidirectional"))
    )
    (net (code "63") (name "Net-(D108-PadC)") (class "Default")
      (node (ref "D108") (pin "C") (pinfunction "C_C") (pintype "passive"))
      (node (ref "K107") (pin "P$1") (pinfunction "P$1_P$1") (pintype "bidirectional"))
    )
    (net (code "64") (name "Net-(D109-PadC)") (class "Default")
      (node (ref "D109") (pin "C") (pinfunction "C_C") (pintype "passive"))
      (node (ref "K106") (pin "P$1") (pinfunction "P$1_P$1") (pintype "bidirectional"))
    )
    (net (code "65") (name "Net-(D110-PadC)") (class "Default")
      (node (ref "D110") (pin "C") (pinfunction "C_C") (pintype "passive"))
      (node (ref "K111") (pin "P$1") (pinfunction "P$1_P$1") (pintype "bidirectional"))
    )
    (net (code "66") (name "Net-(D111-PadC)") (class "Default")
      (node (ref "D111") (pin "C") (pinfunction "C_C") (pintype "passive"))
      (node (ref "K124") (pin "P$1") (pinfunction "P$1_P$1") (pintype "bidirectional"))
    )
    (net (code "67") (name "Net-(D112-PadC)") (class "Default")
      (node (ref "D112") (pin "C") (pinfunction "C_C") (pintype "passive"))
      (node (ref "K125") (pin "P$1") (pinfunction "P$1_P$1") (pintype "bidirectional"))
    )
    (net (code "68") (name "Net-(D113-PadC)") (class "Default")
      (node (ref "D113") (pin "C") (pinfunction "C_C") (pintype "passive"))
      (node (ref "K126") (pin "P$1") (pinfunction "P$1_P$1") (pintype "bidirectional"))
    )
    (net (code "69") (name "Net-(D114-PadC)") (class "Default")
      (node (ref "D114") (pin "C") (pinfunction "C_C") (pintype "passive"))
      (node (ref "K127") (pin "P$1") (pinfunction "P$1_P$1") (pintype "bidirectional"))
    )
    (net (code "70") (name "Net-(D115-PadC)") (class "Default")
      (node (ref "D115") (pin "C") (pinfunction "C_C") (pintype "passive"))
      (node (ref "K104") (pin "P$1") (pinfunction "P$1_P$1") (pintype "bidirectional"))
    )
    (net (code "71") (name "Net-(D116-PadC)") (class "Default")
      (node (ref "D116") (pin "C") (pinfunction "C_C") (pintype "passive"))
      (node (ref "K98") (pin "P$1") (pinfunction "P$1_P$1") (pintype "bidirectional"))
    )
    (net (code "72") (name "Net-(D117-PadC)") (class "Default")
      (node (ref "D117") (pin "C") (pinfunction "C_C") (pintype "passive"))
      (node (ref "K105") (pin "P$1") (pinfunction "P$1_P$1") (pintype "bidirectional"))
    )
    (net (code "73") (name "Net-(D118-PadC)") (class "Default")
      (node (ref "D118") (pin "C") (pinfunction "C_C") (pintype "passive"))
      (node (ref "K112") (pin "P$1") (pinfunction "P$1_P$1") (pintype "bidirectional"))
    )
    (net (code "74") (name "Net-(D119-PadC)") (class "Default")
      (node (ref "D119") (pin "C") (pinfunction "C_C") (pintype "passive"))
      (node (ref "K119") (pin "P$1") (pinfunction "P$1_P$1") (pintype "bidirectional"))
    )
    (net (code "75") (name "Net-(D120-PadC)") (class "Default")
      (node (ref "D120") (pin "C") (pinfunction "C_C") (pintype "passive"))
      (node (ref "K120") (pin "P$1") (pinfunction "P$1_P$1") (pintype "bidirectional"))
    )
    (net (code "76") (name "Net-(D121-PadC)") (class "Default")
      (node (ref "D121") (pin "C") (pinfunction "C_C") (pintype "passive"))
      (node (ref "K113") (pin "P$1") (pinfunction "P$1_P$1") (pintype "bidirectional"))
    )
    (net (code "77") (name "Net-(D122-PadC)") (class "Default")
      (node (ref "D122") (pin "C") (pinfunction "C_C") (pintype "passive"))
      (node (ref "K114") (pin "P$1") (pinfunction "P$1_P$1") (pintype "bidirectional"))
    )
    (net (code "78") (name "Net-(D123-PadC)") (class "Default")
      (node (ref "D123") (pin "C") (pinfunction "C_C") (pintype "passive"))
      (node (ref "K115") (pin "P$1") (pinfunction "P$1_P$1") (pintype "bidirectional"))
    )
    (net (code "79") (name "Net-(D124-PadC)") (class "Default")
      (node (ref "D124") (pin "C") (pinfunction "C_C") (pintype "passive"))
      (node (ref "K116") (pin "P$1") (pinfunction "P$1_P$1") (pintype "bidirectional"))
    )
    (net (code "80") (name "Net-(D125-PadC)") (class "Default")
      (node (ref "D125") (pin "C") (pinfunction "C_C") (pintype "passive"))
      (node (ref "K122") (pin "P$1") (pinfunction "P$1_P$1") (pintype "bidirectional"))
    )
    (net (code "81") (name "Net-(D126-PadC)") (class "Default")
      (node (ref "D126") (pin "C") (pinfunction "C_C") (pintype "passive"))
      (node (ref "K121") (pin "P$1") (pinfunction "P$1_P$1") (pintype "bidirectional"))
    )
    (net (code "82") (name "Net-(D127-PadC)") (class "Default")
      (node (ref "D127") (pin "C") (pinfunction "C_C") (pintype "passive"))
      (node (ref "K123") (pin "P$1") (pinfunction "P$1_P$1") (pintype "bidirectional"))
    )
    (net (code "83") (name "Net-(D128-PadC)") (class "Default")
      (node (ref "D128") (pin "C") (pinfunction "C_C") (pintype "passive"))
      (node (ref "K117") (pin "P$1") (pinfunction "P$1_P$1") (pintype "bidirectional"))
    )
    (net (code "84") (name "Net-(D129-PadC)") (class "Default")
      (node (ref "D129") (pin "C") (pinfunction "C_C") (pintype "passive"))
      (node (ref "K129") (pin "P$1") (pinfunction "P$1_P$1") (pintype "bidirectional"))
    )
    (net (code "85") (name "Net-(D130-PadC)") (class "Default")
      (node (ref "D130") (pin "C") (pinfunction "C_C") (pintype "passive"))
      (node (ref "K130") (pin "P$1") (pinfunction "P$1_P$1") (pintype "bidirectional"))
    )
    (net (code "86") (name "Net-(IC1-(PCI18{slash}INT0)PD2)") (class "Default")
      (node (ref "IC1") (pin "4") (pinfunction "(PCI18/INT0)PD2_4") (pintype "bidirectional"))
      (node (ref "R7") (pin "1") (pinfunction "1_1") (pintype "passive"))
    )
    (net (code "87") (name "Net-(IC1-(PCI19{slash}INT1{slash}OC2B)PD3)") (class "Default")
      (node (ref "IC1") (pin "5") (pinfunction "(PCI19/INT1/OC2B)PD3_5") (pintype "bidirectional"))
      (node (ref "R6") (pin "1") (pinfunction "1_1") (pintype "passive"))
    )
    (net (code "88") (name "Net-(IC1-(PCI20{slash}XCK{slash}T0)PD4)") (class "Default")
      (node (ref "IC1") (pin "6") (pinfunction "(PCI20/XCK/T0)PD4_6") (pintype "bidirectional"))
      (node (ref "LED1") (pin "A") (pinfunction "A_A") (pintype "passive"))
    )
    (net (code "89") (name "Net-(IC1-PB6(XTAL1{slash}TOSC1{slash}PCI6))") (class "Default")
      (node (ref "C9") (pin "1") (pinfunction "1_1") (pintype "passive"))
      (node (ref "IC1") (pin "9") (pinfunction "PB6(XTAL1/TOSC1/PCI6)_9") (pintype "bidirectional"))
      (node (ref "Q1") (pin "2") (pinfunction "2_2") (pintype "passive"))
    )
    (net (code "90") (name "Net-(IC1-PB7(XTAL2{slash}TOSC2{slash}PCI7))") (class "Default")
      (node (ref "C10") (pin "1") (pinfunction "1_1") (pintype "passive"))
      (node (ref "IC1") (pin "10") (pinfunction "PB7(XTAL2/TOSC2/PCI7)_10") (pintype "bidirectional"))
      (node (ref "Q1") (pin "1") (pinfunction "1_1") (pintype "passive"))
    )
    (net (code "91") (name "Net-(IC1-PC6({slash}RESET{slash}PCI14))") (class "Default")
      (node (ref "IC1") (pin "1") (pinfunction "PC6(/RESET/PCI14)_1") (pintype "bidirectional"))
      (node (ref "R5") (pin "2") (pinfunction "2_2") (pintype "passive"))
      (node (ref "S1") (pin "1") (pinfunction "S_1") (pintype "passive"))
      (node (ref "S1") (pin "2") (pinfunction "S1_2") (pintype "passive"))
    )
    (net (code "92") (name "Net-(LED1-PadC)") (class "Default")
      (node (ref "LED1") (pin "C") (pinfunction "C_C") (pintype "passive"))
      (node (ref "R3") (pin "1") (pinfunction "1_1") (pintype "passive"))
    )
    (net (code "93") (name "VCC") (class "Default")
      (node (ref "C3") (pin "1") (pinfunction "1_1") (pintype "passive"))
      (node (ref "C4") (pin "1") (pinfunction "1_1") (pintype "passive"))
      (node (ref "C5") (pin "1") (pinfunction "1_1") (pintype "passive"))
      (node (ref "C6") (pin "1") (pinfunction "1_1") (pintype "passive"))
      (node (ref "C7") (pin "1") (pinfunction "1_1") (pintype "passive"))
      (node (ref "IC1") (pin "20") (pinfunction "AVCC_20") (pintype "bidirectional"))
      (node (ref "IC1") (pin "21") (pinfunction "AREF_21") (pintype "bidirectional"))
      (node (ref "IC1") (pin "7") (pinfunction "VCC_7") (pintype "bidirectional"))
      (node (ref "R2") (pin "1") (pinfunction "1_1") (pintype "passive"))
      (node (ref "R5") (pin "1") (pinfunction "1_1") (pintype "passive"))
      (node (ref "U1") (pin "VBUS1") (pinfunction "VBUS_VBUS1") (pintype "bidirectional"))
    )
    (net (code "94") (name "unconnected-(U1-USBID-PadID1)") (class "Default")
      (node (ref "U1") (pin "ID1") (pinfunction "USBID_ID1") (pintype "bidirectional"))
    )
  )
)
